# Digital_Inputs.net
KiCad netlist of a schematic drawn in Altium Designer
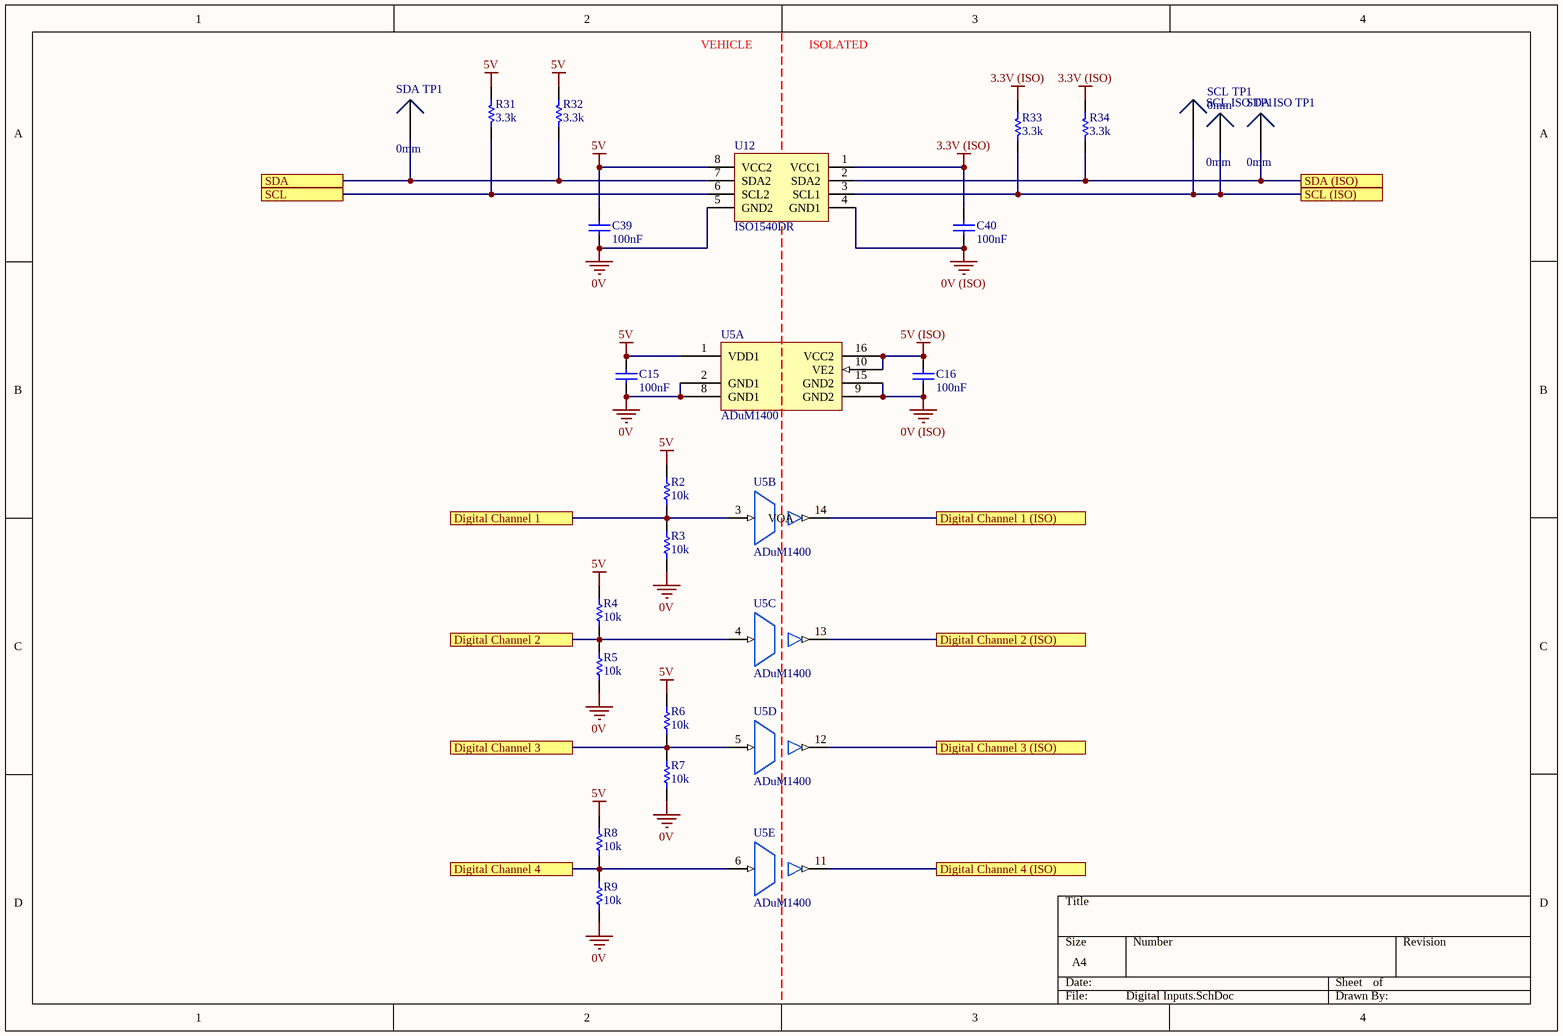
[diagram p0: Digital Inputs.SchDoc]

(export (version "E")
  (design (tool "Eeschema 10.0.6"))
  (components
    (comp (ref "C15")
      (value "100nF")
      (footprint "0805")
      (fields
        (field (name "PART NUMBER") "GCM21BR71E104KA37L")
        (field (name "TOLERANCE") "10%")
        (field (name "MANUFACTURER") "muRata")
      )
      (libsource (lib "ts_20-standard-library") (part "Capacitor"))
    )
    (comp (ref "C16")
      (value "100nF")
      (footprint "0805")
      (fields
        (field (name "PART NUMBER") "GCM21BR71E104KA37L")
        (field (name "TOLERANCE") "10%")
        (field (name "MANUFACTURER") "muRata")
      )
      (libsource (lib "ts_20-standard-library") (part "Capacitor"))
    )
    (comp (ref "C39")
      (value "100nF")
      (footprint "0805")
      (fields
        (field (name "PART NUMBER") "GCM21BR71E104KA37L")
        (field (name "TOLERANCE") "10%")
        (field (name "MANUFACTURER") "muRata")
      )
      (libsource (lib "ts_20-standard-library") (part "Capacitor"))
    )
    (comp (ref "C40")
      (value "100nF")
      (footprint "0805")
      (fields
        (field (name "PART NUMBER") "GCM21BR71E104KA37L")
        (field (name "TOLERANCE") "10%")
        (field (name "MANUFACTURER") "muRata")
      )
      (libsource (lib "ts_20-standard-library") (part "Capacitor"))
    )
    (comp (ref "R2")
      (value "10k")
      (footprint "0805")
      (fields
        (field (name "PART NUMBER") "RC0805FR0710KL")
        (field (name "MANUFACTURER") "YAGEO")
        (field (name "TOLERANCE") "0.01")
      )
      (libsource (lib "ts_20-standard-library") (part "Resistor"))
    )
    (comp (ref "R3")
      (value "10k")
      (footprint "0805")
      (fields
        (field (name "PART NUMBER") "RC0805FR0710KL")
        (field (name "MANUFACTURER") "YAGEO")
        (field (name "TOLERANCE") "0.01")
      )
      (libsource (lib "ts_20-standard-library") (part "Resistor"))
    )
    (comp (ref "R4")
      (value "10k")
      (footprint "0805")
      (fields
        (field (name "PART NUMBER") "RC0805FR0710KL")
        (field (name "MANUFACTURER") "YAGEO")
        (field (name "TOLERANCE") "0.01")
      )
      (libsource (lib "ts_20-standard-library") (part "Resistor"))
    )
    (comp (ref "R5")
      (value "10k")
      (footprint "0805")
      (fields
        (field (name "PART NUMBER") "RC0805FR0710KL")
        (field (name "MANUFACTURER") "YAGEO")
        (field (name "TOLERANCE") "0.01")
      )
      (libsource (lib "ts_20-standard-library") (part "Resistor"))
    )
    (comp (ref "R6")
      (value "10k")
      (footprint "0805")
      (fields
        (field (name "PART NUMBER") "RC0805FR0710KL")
        (field (name "MANUFACTURER") "YAGEO")
        (field (name "TOLERANCE") "0.01")
      )
      (libsource (lib "ts_20-standard-library") (part "Resistor"))
    )
    (comp (ref "R7")
      (value "10k")
      (footprint "0805")
      (fields
        (field (name "PART NUMBER") "RC0805FR0710KL")
        (field (name "MANUFACTURER") "YAGEO")
        (field (name "TOLERANCE") "0.01")
      )
      (libsource (lib "ts_20-standard-library") (part "Resistor"))
    )
    (comp (ref "R8")
      (value "10k")
      (footprint "0805")
      (fields
        (field (name "PART NUMBER") "RC0805FR0710KL")
        (field (name "MANUFACTURER") "YAGEO")
        (field (name "TOLERANCE") "0.01")
      )
      (libsource (lib "ts_20-standard-library") (part "Resistor"))
    )
    (comp (ref "R9")
      (value "10k")
      (footprint "0805")
      (fields
        (field (name "PART NUMBER") "RC0805FR0710KL")
        (field (name "MANUFACTURER") "YAGEO")
        (field (name "TOLERANCE") "0.01")
      )
      (libsource (lib "ts_20-standard-library") (part "Resistor"))
    )
    (comp (ref "R31")
      (value "3.3k")
      (footprint "0805")
      (fields
        (field (name "PART NUMBER") "RC0805FR073K3L")
        (field (name "MANUFACTURER") "YAGEO")
        (field (name "TOLERANCE") "0.01")
      )
      (libsource (lib "ts_20-standard-library") (part "Resistor"))
    )
    (comp (ref "R32")
      (value "3.3k")
      (footprint "0805")
      (fields
        (field (name "PART NUMBER") "RC0805FR073K3L")
        (field (name "MANUFACTURER") "YAGEO")
        (field (name "TOLERANCE") "0.01")
      )
      (libsource (lib "ts_20-standard-library") (part "Resistor"))
    )
    (comp (ref "R33")
      (value "3.3k")
      (footprint "0805")
      (fields
        (field (name "PART NUMBER") "RC0805FR073K3L")
        (field (name "MANUFACTURER") "YAGEO")
        (field (name "TOLERANCE") "0.01")
      )
      (libsource (lib "ts_20-standard-library") (part "Resistor"))
    )
    (comp (ref "R34")
      (value "3.3k")
      (footprint "0805")
      (fields
        (field (name "PART NUMBER") "RC0805FR073K3L")
        (field (name "MANUFACTURER") "YAGEO")
        (field (name "TOLERANCE") "0.01")
      )
      (libsource (lib "ts_20-standard-library") (part "Resistor"))
    )
    (comp (ref "SCL ISO TP1")
      (value "0mm")
      (footprint "SMD Test Point")
      (fields (field (name "PART NUMBER") "SMD Test Point") (field (name "CONTACT") "NA"))
      (libsource (lib "ts_20-standard-connectors") (part "Test Point"))
    )
    (comp (ref "SCL TP1")
      (value "0mm")
      (footprint "SMD Test Point")
      (fields (field (name "PART NUMBER") "SMD Test Point") (field (name "CONTACT") "NA"))
      (libsource (lib "ts_20-standard-connectors") (part "Test Point"))
    )
    (comp (ref "SDA ISO TP1")
      (value "0mm")
      (footprint "SMD Test Point")
      (fields (field (name "PART NUMBER") "SMD Test Point") (field (name "CONTACT") "NA"))
      (libsource (lib "ts_20-standard-connectors") (part "Test Point"))
    )
    (comp (ref "SDA TP1")
      (value "0mm")
      (footprint "SMD Test Point")
      (fields (field (name "PART NUMBER") "SMD Test Point") (field (name "CONTACT") "NA"))
      (libsource (lib "ts_20-standard-connectors") (part "Test Point"))
    )
    (comp (ref "U5")
      (value "ADuM1400")
      (footprint "AD 16-SOIC")
      (fields
        (field (name "MANUFACTURER") "Analog Devices")
        (field (name "DIGIKEY PART NUMBER") "ADUM1400WSRWZ-ND")
      )
      (libsource (lib "ts_20-standard-library") (part "ADuM1400"))
    )
    (comp (ref "U12")
      (value "ISO1540DR")
      (footprint "TI 8-SOIC")
      (description "I2C Digital Isolator (Multichannel)")
      (fields
        (field (name "MANUFACTURER") "Texas Instruments")
        (field (name "DIGIKEY PART NUMBER") "296-34871-1-ND")
      )
      (libsource (lib "ts_20-standard-library") (part "ISO1540DR"))
    )
  )
  (nets
    (net (code "1") (name "/Digital Channel 1") (class "Default")
      (node (ref "R2") (pin "1") (pinfunction "1_1") (pintype "passive"))
      (node (ref "R3") (pin "2") (pinfunction "2_2") (pintype "passive"))
      (node (ref "U5") (pin "3") (pinfunction "VIA_3") (pintype "input"))
    )
    (net (code "2") (name "/Digital Channel 1 (ISO)") (class "Default")
      (node (ref "U5") (pin "14") (pinfunction "VOA_14") (pintype "output"))
    )
    (net (code "3") (name "/Digital Channel 2") (class "Default")
      (node (ref "R4") (pin "1") (pinfunction "1_1") (pintype "passive"))
      (node (ref "R5") (pin "2") (pinfunction "2_2") (pintype "passive"))
      (node (ref "U5") (pin "4") (pinfunction "VIB_4") (pintype "input"))
    )
    (net (code "4") (name "/Digital Channel 2 (ISO)") (class "Default")
      (node (ref "U5") (pin "13") (pinfunction "VOB_13") (pintype "output"))
    )
    (net (code "5") (name "/Digital Channel 3") (class "Default")
      (node (ref "R6") (pin "1") (pinfunction "1_1") (pintype "passive"))
      (node (ref "R7") (pin "2") (pinfunction "2_2") (pintype "passive"))
      (node (ref "U5") (pin "5") (pinfunction "VIC_5") (pintype "input"))
    )
    (net (code "6") (name "/Digital Channel 3 (ISO)") (class "Default")
      (node (ref "U5") (pin "12") (pinfunction "VOC_12") (pintype "output"))
    )
    (net (code "7") (name "/Digital Channel 4") (class "Default")
      (node (ref "R8") (pin "1") (pinfunction "1_1") (pintype "passive"))
      (node (ref "R9") (pin "2") (pinfunction "2_2") (pintype "passive"))
      (node (ref "U5") (pin "6") (pinfunction "VID_6") (pintype "input"))
    )
    (net (code "8") (name "/Digital Channel 4 (ISO)") (class "Default")
      (node (ref "U5") (pin "11") (pinfunction "VOD_11") (pintype "output"))
    )
    (net (code "9") (name "/SCL") (class "Default")
      (node (ref "R31") (pin "1") (pinfunction "1_1") (pintype "passive"))
      (node (ref "U12") (pin "6") (pinfunction "SCL2_6") (pintype "power_in"))
    )
    (net (code "10") (name "/SCL (ISO)") (class "Default")
      (node (ref "R33") (pin "1") (pinfunction "1_1") (pintype "passive"))
      (node (ref "SCL ISO TP1") (pin "1") (pinfunction "1_1") (pintype "passive"))
      (node (ref "SCL TP1") (pin "1") (pinfunction "1_1") (pintype "passive"))
      (node (ref "U12") (pin "3") (pinfunction "SCL1_3") (pintype "power_in"))
    )
    (net (code "11") (name "/SDA") (class "Default")
      (node (ref "R32") (pin "1") (pinfunction "1_1") (pintype "passive"))
      (node (ref "SDA TP1") (pin "1") (pinfunction "1_1") (pintype "passive"))
      (node (ref "U12") (pin "7") (pinfunction "SDA2_7") (pintype "power_in"))
    )
    (net (code "12") (name "/SDA (ISO)") (class "Default")
      (node (ref "R34") (pin "1") (pinfunction "1_1") (pintype "passive"))
      (node (ref "SDA ISO TP1") (pin "1") (pinfunction "1_1") (pintype "passive"))
      (node (ref "U12") (pin "2") (pinfunction "SDA2_2") (pintype "power_in"))
    )
    (net (code "13") (name "0V") (class "Default")
      (node (ref "C15") (pin "1") (pinfunction "1_1") (pintype "passive"))
      (node (ref "C39") (pin "1") (pinfunction "1_1") (pintype "passive"))
      (node (ref "R3") (pin "1") (pinfunction "1_1") (pintype "passive"))
      (node (ref "R5") (pin "1") (pinfunction "1_1") (pintype "passive"))
      (node (ref "R7") (pin "1") (pinfunction "1_1") (pintype "passive"))
      (node (ref "R9") (pin "1") (pinfunction "1_1") (pintype "passive"))
      (node (ref "U12") (pin "5") (pinfunction "GND2_5") (pintype "power_in"))
      (node (ref "U5") (pin "2") (pinfunction "GND1_2") (pintype "power_in"))
      (node (ref "U5") (pin "8") (pinfunction "GND1_8") (pintype "power_in"))
    )
    (net (code "14") (name "0V (ISO)") (class "Default")
      (node (ref "C16") (pin "1") (pinfunction "1_1") (pintype "passive"))
      (node (ref "C40") (pin "1") (pinfunction "1_1") (pintype "passive"))
      (node (ref "U12") (pin "4") (pinfunction "GND1_4") (pintype "power_in"))
      (node (ref "U5") (pin "15") (pinfunction "GND2_15") (pintype "power_in"))
      (node (ref "U5") (pin "9") (pinfunction "GND2_9") (pintype "power_in"))
    )
    (net (code "15") (name "3.3V (ISO)") (class "Default")
      (node (ref "C40") (pin "2") (pinfunction "2_2") (pintype "passive"))
      (node (ref "R33") (pin "2") (pinfunction "2_2") (pintype "passive"))
      (node (ref "R34") (pin "2") (pinfunction "2_2") (pintype "passive"))
      (node (ref "U12") (pin "1") (pinfunction "VCC1_1") (pintype "power_in"))
    )
    (net (code "16") (name "5V") (class "Default")
      (node (ref "C15") (pin "2") (pinfunction "2_2") (pintype "passive"))
      (node (ref "C39") (pin "2") (pinfunction "2_2") (pintype "passive"))
      (node (ref "R2") (pin "2") (pinfunction "2_2") (pintype "passive"))
      (node (ref "R31") (pin "2") (pinfunction "2_2") (pintype "passive"))
      (node (ref "R32") (pin "2") (pinfunction "2_2") (pintype "passive"))
      (node (ref "R4") (pin "2") (pinfunction "2_2") (pintype "passive"))
      (node (ref "R6") (pin "2") (pinfunction "2_2") (pintype "passive"))
      (node (ref "R8") (pin "2") (pinfunction "2_2") (pintype "passive"))
      (node (ref "U12") (pin "8") (pinfunction "VCC2_8") (pintype "power_in"))
      (node (ref "U5") (pin "1") (pinfunction "VDD1_1") (pintype "power_in"))
    )
    (net (code "17") (name "5V (ISO)") (class "Default")
      (node (ref "C16") (pin "2") (pinfunction "2_2") (pintype "passive"))
      (node (ref "U5") (pin "10") (pinfunction "VE2_10") (pintype "input"))
      (node (ref "U5") (pin "16") (pinfunction "VCC2_16") (pintype "power_in"))
    )
  )
)
